# Sterownik_laminatora_PID_v3.net
KiCad netlist of a schematic drawn in EAGLE
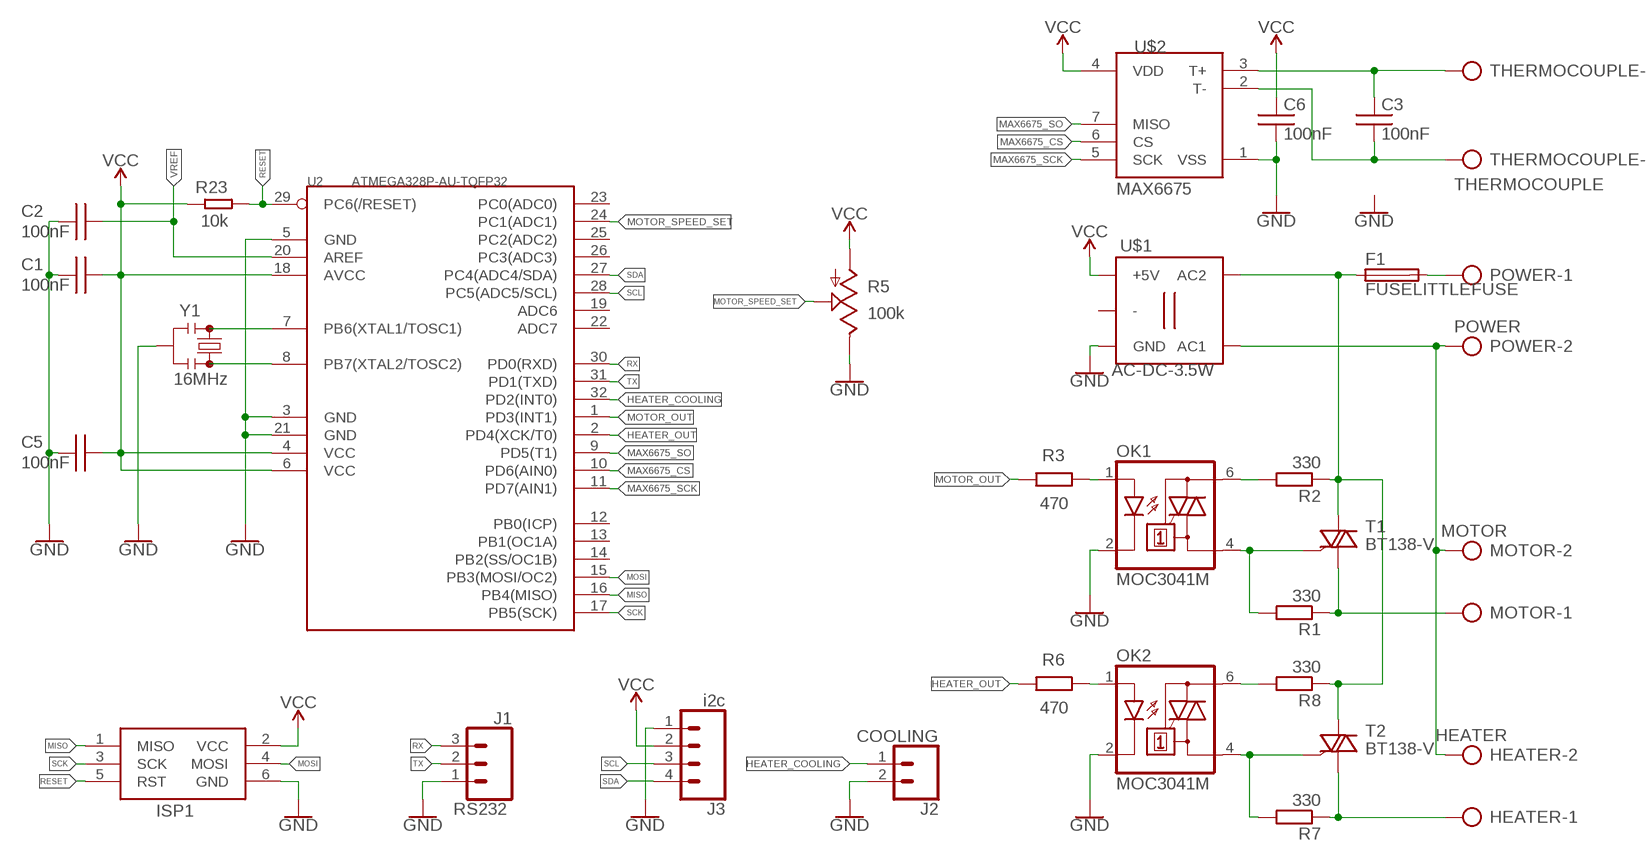
[diagram p0: schematic, sheet 1]

(export (version "E")
  (design (tool "Eeschema 10.0.6"))
  (components
    (comp (ref "C1")
      (value "100nF")
      (footprint "eagle-import:C0805K")
      (libsource (lib "eagle-import") (part "C-C0805K"))
    )
    (comp (ref "C2")
      (value "100nF")
      (footprint "eagle-import:C0805K")
      (libsource (lib "eagle-import") (part "C-C0805K"))
    )
    (comp (ref "C3")
      (value "100nF")
      (footprint "eagle-import:C0805K")
      (libsource (lib "eagle-import") (part "C-C0805K"))
    )
    (comp (ref "C5")
      (value "100nF")
      (footprint "eagle-import:C0805K")
      (libsource (lib "eagle-import") (part "C-C0805K"))
    )
    (comp (ref "C6")
      (value "100nF")
      (footprint "eagle-import:C0805K")
      (libsource (lib "eagle-import") (part "C-C0805K"))
    )
    (comp (ref "F1")
      (value "FUSELITTLEFUSE")
      (footprint "eagle-import:LITTLEFUSE")
      (libsource (lib "eagle-import") (part "FUSELITTLEFUSE"))
    )
    (comp (ref "HEATER")
      (value "HEATER")
      (footprint "eagle-import:AK500_2")
      (libsource (lib "eagle-import") (part "AK500/2"))
    )
    (comp (ref "ISP1")
      (value "AVRISP-6")
      (footprint "eagle-import:AVRISP")
      (libsource (lib "eagle-import") (part "AVRISP-6"))
    )
    (comp (ref "J1")
      (value "RS232")
      (footprint "eagle-import:1X03")
      (libsource (lib "eagle-import") (part "CONN_03"))
    )
    (comp (ref "J2")
      (value "COOLING")
      (footprint "eagle-import:1X02")
      (libsource (lib "eagle-import") (part "CONN_02"))
    )
    (comp (ref "J3")
      (value "i2c")
      (footprint "eagle-import:1X04")
      (libsource (lib "eagle-import") (part "CONN_04PTH"))
    )
    (comp (ref "MOTOR")
      (value "MOTOR")
      (footprint "eagle-import:AK500_2")
      (libsource (lib "eagle-import") (part "AK500/2"))
    )
    (comp (ref "OK1")
      (value "MOC3041M")
      (footprint "eagle-import:DIL06")
      (fields (field (name "MF") "FAIRCHILD SEMICONDUCTOR"))
      (libsource (lib "eagle-import") (part "MOC3041M"))
    )
    (comp (ref "OK2")
      (value "MOC3041M")
      (footprint "eagle-import:DIL06")
      (fields (field (name "MF") "FAIRCHILD SEMICONDUCTOR"))
      (libsource (lib "eagle-import") (part "MOC3041M"))
    )
    (comp (ref "POWER")
      (value "POWER")
      (footprint "eagle-import:AK500_2")
      (libsource (lib "eagle-import") (part "AK500/2"))
    )
    (comp (ref "R1")
      (value "330")
      (footprint "eagle-import:M0805")
      (libsource (lib "eagle-import") (part "R-EU_M0805"))
    )
    (comp (ref "R2")
      (value "330")
      (footprint "eagle-import:0204_7")
      (libsource (lib "eagle-import") (part "R-EU_0204/7"))
    )
    (comp (ref "R3")
      (value "470")
      (footprint "eagle-import:M0805")
      (libsource (lib "eagle-import") (part "R-EU_M0805"))
    )
    (comp (ref "R5")
      (value "100k")
      (footprint "eagle-import:S63S")
      (libsource (lib "eagle-import") (part "TRIM_US-S63S"))
    )
    (comp (ref "R6")
      (value "470")
      (footprint "eagle-import:M0805")
      (libsource (lib "eagle-import") (part "R-EU_M0805"))
    )
    (comp (ref "R7")
      (value "330")
      (footprint "eagle-import:M0805")
      (libsource (lib "eagle-import") (part "R-EU_M0805"))
    )
    (comp (ref "R8")
      (value "330")
      (footprint "eagle-import:0204_7")
      (libsource (lib "eagle-import") (part "R-EU_0204/7"))
    )
    (comp (ref "R23")
      (value "10k")
      (footprint "eagle-import:M0805")
      (libsource (lib "eagle-import") (part "R-M0805"))
    )
    (comp (ref "T1")
      (value "BT138-V")
      (footprint "eagle-import:TO220BV")
      (libsource (lib "eagle-import") (part "BT138-V"))
    )
    (comp (ref "T2")
      (value "BT138-V")
      (footprint "eagle-import:TO220BV")
      (libsource (lib "eagle-import") (part "BT138-V"))
    )
    (comp (ref "THERMOCOUPLE")
      (value "THERMOCOUPLE")
      (footprint "eagle-import:AK500_2")
      (libsource (lib "eagle-import") (part "AK500/2"))
    )
    (comp (ref "U$1")
      (value "AC-DC-3.5W")
      (footprint "eagle-import:AC-DC-3.5W")
      (libsource (lib "eagle-import") (part "AC-DC-3.5W"))
    )
    (comp (ref "U$2")
      (value "MAX6675")
      (footprint "eagle-import:SO08")
      (libsource (lib "eagle-import") (part "MAX6675"))
    )
    (comp (ref "U2")
      (value "ATMEGA328P-AU-TQFP32")
      (footprint "eagle-import:TQFP32-0.8-7X7MM")
      (fields (field (name "MPN") "ATMEGA328P-AU"))
      (libsource (lib "eagle-import") (part "MCU-ATMEGA328P-AU(TQFP32)"))
    )
    (comp (ref "Y1")
      (value "16MHz")
      (footprint "eagle-import:RESONATOR-SMD-3.2X1.3")
      (libsource (lib "eagle-import") (part "RESONATOR-16MHZSMD_3.2X1.3"))
    )
  )
  (nets
    (net (code "1") (name "GND") (class "Default")
      (node (ref "C1") (pin "2") (pinfunction "2_2") (pintype "passive"))
      (node (ref "C2") (pin "2") (pinfunction "2_2") (pintype "passive"))
      (node (ref "C5") (pin "1") (pinfunction "1_1") (pintype "passive"))
      (node (ref "C6") (pin "2") (pinfunction "2_2") (pintype "passive"))
      (node (ref "ISP1") (pin "6") (pinfunction "GND_6") (pintype "power_in"))
      (node (ref "J1") (pin "1") (pinfunction "1_1") (pintype "passive"))
      (node (ref "J2") (pin "2") (pinfunction "2_2") (pintype "passive"))
      (node (ref "J3") (pin "1") (pinfunction "1_1") (pintype "passive"))
      (node (ref "OK1") (pin "2") (pinfunction "C_2") (pintype "passive"))
      (node (ref "OK2") (pin "2") (pinfunction "C_2") (pintype "passive"))
      (node (ref "R5") (pin "E") (pinfunction "E_E") (pintype "passive"))
      (node (ref "U$1") (pin "J2.1") (pinfunction "GND_J2.1") (pintype "power_in"))
      (node (ref "U$2") (pin "1") (pinfunction "VSS_1") (pintype "bidirectional"))
      (node (ref "U2") (pin "21") (pinfunction "GND_21") (pintype "bidirectional"))
      (node (ref "U2") (pin "3") (pinfunction "GND_3") (pintype "bidirectional"))
      (node (ref "U2") (pin "5") (pinfunction "GND_5") (pintype "bidirectional"))
      (node (ref "Y1") (pin "2") (pinfunction "2_2") (pintype "passive"))
    )
    (net (code "2") (name "HEATER_COOLING") (class "Default")
      (node (ref "J2") (pin "1") (pinfunction "1_1") (pintype "passive"))
      (node (ref "U2") (pin "32") (pinfunction "PD2(INT0)_32") (pintype "bidirectional"))
    )
    (net (code "3") (name "HEATER_OUT") (class "Default")
      (node (ref "R6") (pin "2") (pinfunction "2_2") (pintype "passive"))
      (node (ref "U2") (pin "2") (pinfunction "PD4(XCK/T0)_2") (pintype "bidirectional"))
    )
    (net (code "4") (name "MAX6675_CS") (class "Default")
      (node (ref "U$2") (pin "6") (pinfunction "CS_6") (pintype "bidirectional"))
      (node (ref "U2") (pin "10") (pinfunction "PD6(AIN0)_10") (pintype "bidirectional"))
    )
    (net (code "5") (name "MAX6675_SCK") (class "Default")
      (node (ref "U$2") (pin "5") (pinfunction "SCK_5") (pintype "bidirectional"))
      (node (ref "U2") (pin "11") (pinfunction "PD7(AIN1)_11") (pintype "bidirectional"))
    )
    (net (code "6") (name "MAX6675_SO") (class "Default")
      (node (ref "U$2") (pin "7") (pinfunction "MISO_7") (pintype "bidirectional"))
      (node (ref "U2") (pin "9") (pinfunction "PD5(T1)_9") (pintype "bidirectional"))
    )
    (net (code "7") (name "MISO") (class "Default")
      (node (ref "ISP1") (pin "1") (pinfunction "MISO_1") (pintype "input"))
      (node (ref "U2") (pin "16") (pinfunction "PB4(MISO)_16") (pintype "bidirectional"))
    )
    (net (code "8") (name "MOSI") (class "Default")
      (node (ref "ISP1") (pin "4") (pinfunction "MOSI_4") (pintype "output"))
      (node (ref "U2") (pin "15") (pinfunction "PB3(MOSI/OC2)_15") (pintype "bidirectional"))
    )
    (net (code "9") (name "MOTOR_OUT") (class "Default")
      (node (ref "R3") (pin "2") (pinfunction "2_2") (pintype "passive"))
      (node (ref "U2") (pin "1") (pinfunction "PD3(INT1)_1") (pintype "bidirectional"))
    )
    (net (code "10") (name "MOTOR_SPEED_SET") (class "Default")
      (node (ref "R5") (pin "S") (pinfunction "S_S") (pintype "passive"))
      (node (ref "U2") (pin "24") (pinfunction "PC1(ADC1)_24") (pintype "bidirectional"))
    )
    (net (code "11") (name "Net-(HEATERA-KL)") (class "Default")
      (node (ref "HEATER") (pin "1") (pinfunction "KL_1") (pintype "passive"))
      (node (ref "R7") (pin "1") (pinfunction "1_1") (pintype "passive"))
      (node (ref "T2") (pin "T1") (pinfunction "A1_T1") (pintype "passive"))
    )
    (net (code "12") (name "Net-(HEATERB-KL)") (class "Default")
      (node (ref "HEATER") (pin "2") (pinfunction "KL_2") (pintype "passive"))
      (node (ref "MOTOR") (pin "2") (pinfunction "KL_2") (pintype "passive"))
      (node (ref "POWER") (pin "2") (pinfunction "KL_2") (pintype "passive"))
      (node (ref "U$1") (pin "J1.1") (pinfunction "AC1_J1.1") (pintype "bidirectional"))
    )
    (net (code "13") (name "Net-(MOTORA-KL)") (class "Default")
      (node (ref "MOTOR") (pin "1") (pinfunction "KL_1") (pintype "passive"))
      (node (ref "R1") (pin "1") (pinfunction "1_1") (pintype "passive"))
      (node (ref "T1") (pin "T1") (pinfunction "A1_T1") (pintype "passive"))
    )
    (net (code "14") (name "Net-(OK1-A)") (class "Default")
      (node (ref "OK1") (pin "1") (pinfunction "A_1") (pintype "passive"))
      (node (ref "R3") (pin "1") (pinfunction "1_1") (pintype "passive"))
    )
    (net (code "15") (name "Net-(OK1-A1)") (class "Default")
      (node (ref "OK1") (pin "4") (pinfunction "A1_4") (pintype "passive"))
      (node (ref "R1") (pin "2") (pinfunction "2_2") (pintype "passive"))
      (node (ref "T1") (pin "G") (pinfunction "G_G") (pintype "passive"))
    )
    (net (code "16") (name "Net-(OK1-A2)") (class "Default")
      (node (ref "OK1") (pin "6") (pinfunction "A2_6") (pintype "passive"))
      (node (ref "R2") (pin "2") (pinfunction "2_2") (pintype "passive"))
    )
    (net (code "17") (name "Net-(OK2-A)") (class "Default")
      (node (ref "OK2") (pin "1") (pinfunction "A_1") (pintype "passive"))
      (node (ref "R6") (pin "1") (pinfunction "1_1") (pintype "passive"))
    )
    (net (code "18") (name "Net-(OK2-A1)") (class "Default")
      (node (ref "OK2") (pin "4") (pinfunction "A1_4") (pintype "passive"))
      (node (ref "R7") (pin "2") (pinfunction "2_2") (pintype "passive"))
      (node (ref "T2") (pin "G") (pinfunction "G_G") (pintype "passive"))
    )
    (net (code "19") (name "Net-(OK2-A2)") (class "Default")
      (node (ref "OK2") (pin "6") (pinfunction "A2_6") (pintype "passive"))
      (node (ref "R8") (pin "2") (pinfunction "2_2") (pintype "passive"))
    )
    (net (code "20") (name "Net-(POWERA-KL)") (class "Default")
      (node (ref "F1") (pin "2") (pinfunction "2_2") (pintype "passive"))
      (node (ref "POWER") (pin "1") (pinfunction "KL_1") (pintype "passive"))
    )
    (net (code "21") (name "Net-(T1-A2)") (class "Default")
      (node (ref "F1") (pin "1") (pinfunction "1_1") (pintype "passive"))
      (node (ref "R2") (pin "1") (pinfunction "1_1") (pintype "passive"))
      (node (ref "R8") (pin "1") (pinfunction "1_1") (pintype "passive"))
      (node (ref "T1") (pin "T2") (pinfunction "A2_T2") (pintype "passive"))
      (node (ref "T2") (pin "T2") (pinfunction "A2_T2") (pintype "passive"))
      (node (ref "U$1") (pin "J1.2") (pinfunction "AC2_J1.2") (pintype "bidirectional"))
    )
    (net (code "22") (name "Net-(THERMOCOUPLEA-KL)") (class "Default")
      (node (ref "C3") (pin "1") (pinfunction "1_1") (pintype "passive"))
      (node (ref "THERMOCOUPLE") (pin "1") (pinfunction "KL_1") (pintype "passive"))
      (node (ref "U$2") (pin "3") (pinfunction "T+_3") (pintype "bidirectional"))
    )
    (net (code "23") (name "Net-(THERMOCOUPLEB-KL)") (class "Default")
      (node (ref "C3") (pin "2") (pinfunction "2_2") (pintype "passive"))
      (node (ref "THERMOCOUPLE") (pin "2") (pinfunction "KL_2") (pintype "passive"))
      (node (ref "U$2") (pin "2") (pinfunction "T-_2") (pintype "bidirectional"))
    )
    (net (code "24") (name "Net-(U2-PB6(XTAL1{slash}TOSC1))") (class "Default")
      (node (ref "U2") (pin "7") (pinfunction "PB6(XTAL1/TOSC1)_7") (pintype "bidirectional"))
      (node (ref "Y1") (pin "1") (pinfunction "1_1") (pintype "passive"))
    )
    (net (code "25") (name "Net-(U2-PB7(XTAL2{slash}TOSC2))") (class "Default")
      (node (ref "U2") (pin "8") (pinfunction "PB7(XTAL2/TOSC2)_8") (pintype "bidirectional"))
      (node (ref "Y1") (pin "3") (pinfunction "3_3") (pintype "passive"))
    )
    (net (code "26") (name "RESET") (class "Default")
      (node (ref "ISP1") (pin "5") (pinfunction "RST_5") (pintype "output"))
      (node (ref "R23") (pin "2") (pinfunction "2_2") (pintype "passive"))
      (node (ref "U2") (pin "29") (pinfunction "PC6(/RESET)_29") (pintype "bidirectional"))
    )
    (net (code "27") (name "RX") (class "Default")
      (node (ref "J1") (pin "3") (pinfunction "3_3") (pintype "passive"))
      (node (ref "U2") (pin "30") (pinfunction "PD0(RXD)_30") (pintype "bidirectional"))
    )
    (net (code "28") (name "SCK") (class "Default")
      (node (ref "ISP1") (pin "3") (pinfunction "SCK_3") (pintype "output"))
      (node (ref "U2") (pin "17") (pinfunction "PB5(SCK)_17") (pintype "bidirectional"))
    )
    (net (code "29") (name "SCL") (class "Default")
      (node (ref "J3") (pin "3") (pinfunction "3_3") (pintype "passive"))
      (node (ref "U2") (pin "28") (pinfunction "PC5(ADC5/SCL)_28") (pintype "bidirectional"))
    )
    (net (code "30") (name "SDA") (class "Default")
      (node (ref "J3") (pin "4") (pinfunction "4_4") (pintype "passive"))
      (node (ref "U2") (pin "27") (pinfunction "PC4(ADC4/SDA)_27") (pintype "bidirectional"))
    )
    (net (code "31") (name "TX") (class "Default")
      (node (ref "J1") (pin "2") (pinfunction "2_2") (pintype "passive"))
      (node (ref "U2") (pin "31") (pinfunction "PD1(TXD)_31") (pintype "bidirectional"))
    )
    (net (code "32") (name "VCC") (class "Default")
      (node (ref "C1") (pin "1") (pinfunction "1_1") (pintype "passive"))
      (node (ref "C5") (pin "2") (pinfunction "2_2") (pintype "passive"))
      (node (ref "C6") (pin "1") (pinfunction "1_1") (pintype "passive"))
      (node (ref "ISP1") (pin "2") (pinfunction "VCC_2") (pintype "power_in"))
      (node (ref "J3") (pin "2") (pinfunction "2_2") (pintype "passive"))
      (node (ref "R23") (pin "1") (pinfunction "1_1") (pintype "passive"))
      (node (ref "R5") (pin "A") (pinfunction "A_A") (pintype "passive"))
      (node (ref "U$1") (pin "J2.3") (pinfunction "+5V_J2.3") (pintype "power_in"))
      (node (ref "U$2") (pin "4") (pinfunction "VDD_4") (pintype "bidirectional"))
      (node (ref "U2") (pin "18") (pinfunction "AVCC_18") (pintype "bidirectional"))
      (node (ref "U2") (pin "4") (pinfunction "VCC_4") (pintype "bidirectional"))
      (node (ref "U2") (pin "6") (pinfunction "VCC_6") (pintype "bidirectional"))
    )
    (net (code "33") (name "VREF") (class "Default")
      (node (ref "C2") (pin "1") (pinfunction "1_1") (pintype "passive"))
      (node (ref "U2") (pin "20") (pinfunction "AREF_20") (pintype "bidirectional"))
    )
    (net (code "34") (name "unconnected-(U$1---PadJ2.2)") (class "Default")
      (node (ref "U$1") (pin "J2.2") (pinfunction "-_J2.2") (pintype "bidirectional"))
    )
    (net (code "35") (name "unconnected-(U2-ADC6-Pad19)") (class "Default")
      (node (ref "U2") (pin "19") (pinfunction "ADC6_19") (pintype "bidirectional"))
    )
    (net (code "36") (name "unconnected-(U2-ADC7-Pad22)") (class "Default")
      (node (ref "U2") (pin "22") (pinfunction "ADC7_22") (pintype "bidirectional"))
    )
    (net (code "37") (name "unconnected-(U2-PB0(ICP)-Pad12)") (class "Default")
      (node (ref "U2") (pin "12") (pinfunction "PB0(ICP)_12") (pintype "bidirectional"))
    )
    (net (code "38") (name "unconnected-(U2-PB1(OC1A)-Pad13)") (class "Default")
      (node (ref "U2") (pin "13") (pinfunction "PB1(OC1A)_13") (pintype "bidirectional"))
    )
    (net (code "39") (name "unconnected-(U2-PB2(SS{slash}OC1B)-Pad14)") (class "Default")
      (node (ref "U2") (pin "14") (pinfunction "PB2(SS/OC1B)_14") (pintype "bidirectional"))
    )
    (net (code "40") (name "unconnected-(U2-PC0(ADC0)-Pad23)") (class "Default")
      (node (ref "U2") (pin "23") (pinfunction "PC0(ADC0)_23") (pintype "bidirectional"))
    )
    (net (code "41") (name "unconnected-(U2-PC2(ADC2)-Pad25)") (class "Default")
      (node (ref "U2") (pin "25") (pinfunction "PC2(ADC2)_25") (pintype "bidirectional"))
    )
    (net (code "42") (name "unconnected-(U2-PC3(ADC3)-Pad26)") (class "Default")
      (node (ref "U2") (pin "26") (pinfunction "PC3(ADC3)_26") (pintype "bidirectional"))
    )
  )
)
